# Flight_Controller.net
KiCad netlist of a schematic drawn in EAGLE
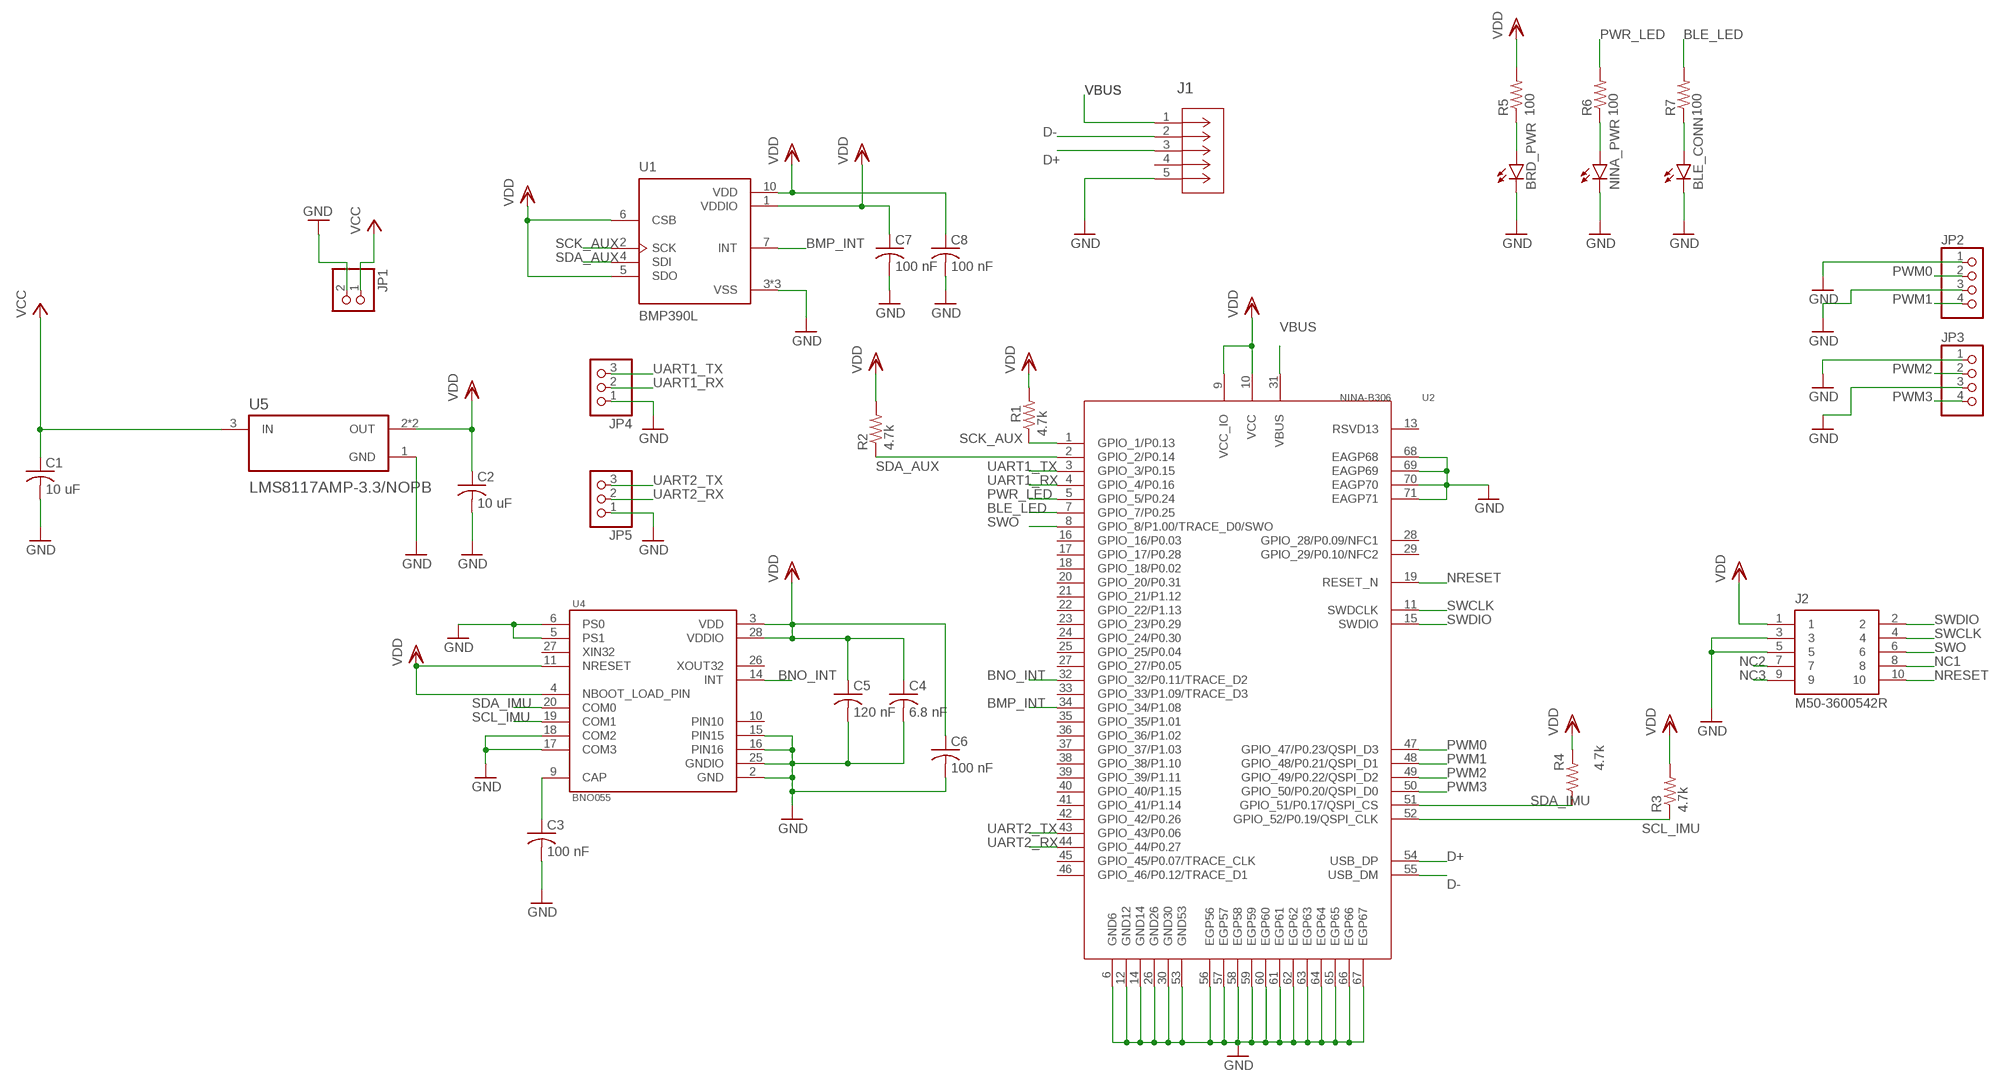
[diagram p0: schematic, sheet 1]

(export (version "E")
  (design (tool "Eeschema 10.0.6"))
  (components
    (comp (ref "BLE_CONN")
      (value "LEDCHIPLED_1206")
      (footprint "eagle-import:CHIPLED_1206")
      (libsource (lib "eagle-import") (part "LEDCHIPLED_1206"))
    )
    (comp (ref "BRD_PWR")
      (value "LEDCHIPLED_1206")
      (footprint "eagle-import:CHIPLED_1206")
      (libsource (lib "eagle-import") (part "LEDCHIPLED_1206"))
    )
    (comp (ref "C1")
      (value "10 uF")
      (footprint "eagle-import:C1206")
      (libsource (lib "eagle-import") (part "C-USC1206"))
    )
    (comp (ref "C2")
      (value "10 uF")
      (footprint "eagle-import:C1206")
      (libsource (lib "eagle-import") (part "C-USC1206"))
    )
    (comp (ref "C3")
      (value "100 nF")
      (footprint "eagle-import:C1206")
      (libsource (lib "eagle-import") (part "C-USC1206"))
    )
    (comp (ref "C4")
      (value "6.8 nF")
      (footprint "eagle-import:C1206")
      (libsource (lib "eagle-import") (part "C-USC1206"))
    )
    (comp (ref "C5")
      (value "120 nF")
      (footprint "eagle-import:C1206")
      (libsource (lib "eagle-import") (part "C-USC1206"))
    )
    (comp (ref "C6")
      (value "100 nF")
      (footprint "eagle-import:C1206")
      (libsource (lib "eagle-import") (part "C-USC1206"))
    )
    (comp (ref "C7")
      (value "100 nF")
      (footprint "eagle-import:C1206")
      (libsource (lib "eagle-import") (part "C-USC1206"))
    )
    (comp (ref "C8")
      (value "100 nF")
      (footprint "eagle-import:C1206")
      (libsource (lib "eagle-import") (part "C-USC1206"))
    )
    (comp (ref "J1")
      (value "ZX62-AB-5PA(31)")
      (footprint "eagle-import:CONN5_ZX62-AB-5PA_HIR")
      (fields (field (name "COPYRIGHT") "Copyright (C) 2022 Ultra Librarian. All rights reserved."))
      (libsource (lib "eagle-import") (part "ZX62-AB-5PA(31)"))
    )
    (comp (ref "J2")
      (value "M50-3600542R")
      (footprint "eagle-import:HARWIN_M50-3600542R")
      (fields (field (name "MF") "Harwin Inc."))
      (libsource (lib "eagle-import") (part "M50-3600542R"))
    )
    (comp (ref "JP1")
      (value "PINHD-1X2")
      (footprint "eagle-import:1X02")
      (libsource (lib "eagle-import") (part "PINHD-1X2"))
    )
    (comp (ref "JP2")
      (value "PINHD-1X4")
      (footprint "eagle-import:1X04")
      (libsource (lib "eagle-import") (part "PINHD-1X4"))
    )
    (comp (ref "JP3")
      (value "PINHD-1X4")
      (footprint "eagle-import:1X04")
      (libsource (lib "eagle-import") (part "PINHD-1X4"))
    )
    (comp (ref "JP4")
      (value "PINHD-1X3")
      (footprint "eagle-import:1X03")
      (libsource (lib "eagle-import") (part "PINHD-1X3"))
    )
    (comp (ref "JP5")
      (value "PINHD-1X3")
      (footprint "eagle-import:1X03")
      (libsource (lib "eagle-import") (part "PINHD-1X3"))
    )
    (comp (ref "NINA_PWR")
      (value "LEDCHIPLED_1206")
      (footprint "eagle-import:CHIPLED_1206")
      (libsource (lib "eagle-import") (part "LEDCHIPLED_1206"))
    )
    (comp (ref "R1")
      (value "4.7k")
      (footprint "eagle-import:R1206")
      (libsource (lib "eagle-import") (part "R-US_R1206"))
    )
    (comp (ref "R2")
      (value "4.7k")
      (footprint "eagle-import:R1206")
      (libsource (lib "eagle-import") (part "R-US_R1206"))
    )
    (comp (ref "R3")
      (value "4.7k")
      (footprint "eagle-import:R1206")
      (libsource (lib "eagle-import") (part "R-US_R1206"))
    )
    (comp (ref "R4")
      (value "4.7k")
      (footprint "eagle-import:R1206")
      (libsource (lib "eagle-import") (part "R-US_R1206"))
    )
    (comp (ref "R5")
      (value "100")
      (footprint "eagle-import:R1206")
      (libsource (lib "eagle-import") (part "R-US_R1206"))
    )
    (comp (ref "R6")
      (value "100")
      (footprint "eagle-import:R1206")
      (libsource (lib "eagle-import") (part "R-US_R1206"))
    )
    (comp (ref "R7")
      (value "100")
      (footprint "eagle-import:R1206")
      (libsource (lib "eagle-import") (part "R-US_R1206"))
    )
    (comp (ref "U1")
      (value "BMP390L")
      (footprint "eagle-import:XDCR_BMP390L")
      (fields (field (name "MF") "Bosch Sensortec"))
      (libsource (lib "eagle-import") (part "BMP390L"))
    )
    (comp (ref "U2")
      (value "NINA-B306")
      (footprint "eagle-import:NINA_LGA71R_1500X1000X223_PCB")
      (fields (field (name "MANUFACTURER") "u-blox"))
      (libsource (lib "eagle-import") (part "NINA-B306NINA-B306_NINA_LGA71R_1500X1000X223_PCB"))
    )
    (comp (ref "U4")
      (value "BNO055")
      (footprint "eagle-import:LGA28R50P4X10_380X520X100")
      (fields (field (name "MF") "Bosch"))
      (libsource (lib "eagle-import") (part "BNO055"))
    )
    (comp (ref "U5")
      (value "LMS8117AMP-3.3/NOPB")
      (footprint "eagle-import:SOT230P700X180-4N")
      (fields (field (name "MF") "Texas Instruments"))
      (libsource (lib "eagle-import") (part "LMS8117AMP-3.3/NOPB"))
    )
  )
  (nets
    (net (code "1") (name "/BLE_LED") (class "Default")
      (node (ref "R7") (pin "2") (pinfunction "2_2") (pintype "passive"))
      (node (ref "U2") (pin "7") (pinfunction "GPIO_7/P0.25_7") (pintype "bidirectional"))
    )
    (net (code "2") (name "/BMP_INT") (class "Default")
      (node (ref "U1") (pin "7") (pinfunction "INT_7") (pintype "output"))
      (node (ref "U2") (pin "34") (pinfunction "GPIO_34/P1.08_34") (pintype "bidirectional"))
    )
    (net (code "3") (name "/BNO_INT") (class "Default")
      (node (ref "U2") (pin "32") (pinfunction "GPIO_32/P0.11/TRACE_D2_32") (pintype "bidirectional"))
      (node (ref "U4") (pin "14") (pinfunction "INT_14") (pintype "output"))
    )
    (net (code "4") (name "/D+") (class "Default")
      (node (ref "J1") (pin "3") (pinfunction "D+_3") (pintype "passive"))
      (node (ref "U2") (pin "54") (pinfunction "USB_DP_54") (pintype "bidirectional"))
    )
    (net (code "5") (name "/D-") (class "Default")
      (node (ref "J1") (pin "2") (pinfunction "D-_2") (pintype "passive"))
      (node (ref "U2") (pin "55") (pinfunction "USB_DM_55") (pintype "bidirectional"))
    )
    (net (code "6") (name "/NC1") (class "Default")
      (node (ref "J2") (pin "8") (pinfunction "8_8") (pintype "passive"))
    )
    (net (code "7") (name "/NC2") (class "Default")
      (node (ref "J2") (pin "7") (pinfunction "7_7") (pintype "passive"))
    )
    (net (code "8") (name "/NC3") (class "Default")
      (node (ref "J2") (pin "9") (pinfunction "9_9") (pintype "passive"))
    )
    (net (code "9") (name "/NRESET") (class "Default")
      (node (ref "J2") (pin "10") (pinfunction "10_10") (pintype "passive"))
      (node (ref "U2") (pin "19") (pinfunction "RESET_N_19") (pintype "input"))
    )
    (net (code "10") (name "/PIN10") (class "Default")
      (node (ref "U4") (pin "10") (pinfunction "PIN10_10") (pintype "power_in"))
    )
    (net (code "11") (name "/PWM0") (class "Default")
      (node (ref "JP2") (pin "2") (pinfunction "2_2") (pintype "passive"))
      (node (ref "U2") (pin "47") (pinfunction "GPIO_47/P0.23/QSPI_D3_47") (pintype "bidirectional"))
    )
    (net (code "12") (name "/PWM1") (class "Default")
      (node (ref "JP2") (pin "4") (pinfunction "4_4") (pintype "passive"))
      (node (ref "U2") (pin "48") (pinfunction "GPIO_48/P0.21/QSPI_D1_48") (pintype "bidirectional"))
    )
    (net (code "13") (name "/PWM2") (class "Default")
      (node (ref "JP3") (pin "2") (pinfunction "2_2") (pintype "passive"))
      (node (ref "U2") (pin "49") (pinfunction "GPIO_49/P0.22/QSPI_D2_49") (pintype "bidirectional"))
    )
    (net (code "14") (name "/PWM3") (class "Default")
      (node (ref "JP3") (pin "4") (pinfunction "4_4") (pintype "passive"))
      (node (ref "U2") (pin "50") (pinfunction "GPIO_50/P0.20/QSPI_D0_50") (pintype "bidirectional"))
    )
    (net (code "15") (name "/PWR_LED") (class "Default")
      (node (ref "R6") (pin "2") (pinfunction "2_2") (pintype "passive"))
      (node (ref "U2") (pin "5") (pinfunction "GPIO_5/P0.24_5") (pintype "bidirectional"))
    )
    (net (code "16") (name "/SCK_AUX") (class "Default")
      (node (ref "R1") (pin "1") (pinfunction "1_1") (pintype "passive"))
      (node (ref "U1") (pin "2") (pinfunction "SCK_2") (pintype "input"))
      (node (ref "U2") (pin "1") (pinfunction "GPIO_1/P0.13_1") (pintype "bidirectional"))
    )
    (net (code "17") (name "/SCL_IMU") (class "Default")
      (node (ref "R3") (pin "1") (pinfunction "1_1") (pintype "passive"))
      (node (ref "U2") (pin "52") (pinfunction "GPIO_52/P0.19/QSPI_CLK_52") (pintype "bidirectional"))
      (node (ref "U4") (pin "19") (pinfunction "COM1_19") (pintype "bidirectional"))
    )
    (net (code "18") (name "/SDA_AUX") (class "Default")
      (node (ref "R2") (pin "1") (pinfunction "1_1") (pintype "passive"))
      (node (ref "U1") (pin "4") (pinfunction "SDI_4") (pintype "input"))
      (node (ref "U2") (pin "2") (pinfunction "GPIO_2/P0.14_2") (pintype "bidirectional"))
    )
    (net (code "19") (name "/SDA_IMU") (class "Default")
      (node (ref "R4") (pin "1") (pinfunction "1_1") (pintype "passive"))
      (node (ref "U2") (pin "51") (pinfunction "GPIO_51/P0.17/QSPI_CS_51") (pintype "bidirectional"))
      (node (ref "U4") (pin "20") (pinfunction "COM0_20") (pintype "bidirectional"))
    )
    (net (code "20") (name "/SWCLK") (class "Default")
      (node (ref "J2") (pin "4") (pinfunction "4_4") (pintype "passive"))
      (node (ref "U2") (pin "11") (pinfunction "SWDCLK_11") (pintype "input"))
    )
    (net (code "21") (name "/SWDIO") (class "Default")
      (node (ref "J2") (pin "2") (pinfunction "2_2") (pintype "passive"))
      (node (ref "U2") (pin "15") (pinfunction "SWDIO_15") (pintype "bidirectional"))
    )
    (net (code "22") (name "/SWO") (class "Default")
      (node (ref "J2") (pin "6") (pinfunction "6_6") (pintype "passive"))
      (node (ref "U2") (pin "8") (pinfunction "GPIO_8/P1.00/TRACE_D0/SWO_8") (pintype "bidirectional"))
    )
    (net (code "23") (name "/UART1_RX") (class "Default")
      (node (ref "JP4") (pin "2") (pinfunction "2_2") (pintype "passive"))
      (node (ref "U2") (pin "4") (pinfunction "GPIO_4/P0.16_4") (pintype "bidirectional"))
    )
    (net (code "24") (name "/UART1_TX") (class "Default")
      (node (ref "JP4") (pin "3") (pinfunction "3_3") (pintype "passive"))
      (node (ref "U2") (pin "3") (pinfunction "GPIO_3/P0.15_3") (pintype "bidirectional"))
    )
    (net (code "25") (name "/UART2_RX") (class "Default")
      (node (ref "JP5") (pin "2") (pinfunction "2_2") (pintype "passive"))
      (node (ref "U2") (pin "44") (pinfunction "GPIO_44/P0.27_44") (pintype "bidirectional"))
    )
    (net (code "26") (name "/UART2_TX") (class "Default")
      (node (ref "JP5") (pin "3") (pinfunction "3_3") (pintype "passive"))
      (node (ref "U2") (pin "43") (pinfunction "GPIO_43/P0.06_43") (pintype "bidirectional"))
    )
    (net (code "27") (name "/VBUS") (class "Default")
      (node (ref "J1") (pin "1") (pinfunction "VCC_1") (pintype "passive"))
      (node (ref "U2") (pin "31") (pinfunction "VBUS_31") (pintype "power_in"))
    )
    (net (code "28") (name "GND") (class "Default")
      (node (ref "BLE_CONN") (pin "C") (pinfunction "C_C") (pintype "passive"))
      (node (ref "BRD_PWR") (pin "C") (pinfunction "C_C") (pintype "passive"))
      (node (ref "C1") (pin "2") (pinfunction "2_2") (pintype "passive"))
      (node (ref "C2") (pin "2") (pinfunction "2_2") (pintype "passive"))
      (node (ref "C3") (pin "2") (pinfunction "2_2") (pintype "passive"))
      (node (ref "C4") (pin "2") (pinfunction "2_2") (pintype "passive"))
      (node (ref "C5") (pin "2") (pinfunction "2_2") (pintype "passive"))
      (node (ref "C6") (pin "2") (pinfunction "2_2") (pintype "passive"))
      (node (ref "C7") (pin "2") (pinfunction "2_2") (pintype "passive"))
      (node (ref "C8") (pin "2") (pinfunction "2_2") (pintype "passive"))
      (node (ref "J1") (pin "5") (pinfunction "GND_5") (pintype "passive"))
      (node (ref "J2") (pin "3") (pinfunction "3_3") (pintype "passive"))
      (node (ref "J2") (pin "5") (pinfunction "5_5") (pintype "passive"))
      (node (ref "JP1") (pin "2") (pinfunction "2_2") (pintype "passive"))
      (node (ref "JP2") (pin "1") (pinfunction "1_1") (pintype "passive"))
      (node (ref "JP2") (pin "3") (pinfunction "3_3") (pintype "passive"))
      (node (ref "JP3") (pin "1") (pinfunction "1_1") (pintype "passive"))
      (node (ref "JP3") (pin "3") (pinfunction "3_3") (pintype "passive"))
      (node (ref "JP4") (pin "1") (pinfunction "1_1") (pintype "passive"))
      (node (ref "JP5") (pin "1") (pinfunction "1_1") (pintype "passive"))
      (node (ref "NINA_PWR") (pin "C") (pinfunction "C_C") (pintype "passive"))
      (node (ref "U1") (pin "3") (pinfunction "VSS_3") (pintype "power_in"))
      (node (ref "U1") (pin "8") (pinfunction "VSS_8") (pintype "power_in"))
      (node (ref "U1") (pin "9") (pinfunction "VSS_9") (pintype "power_in"))
      (node (ref "U2") (pin "12") (pinfunction "GND12_12") (pintype "power_in"))
      (node (ref "U2") (pin "14") (pinfunction "GND14_14") (pintype "power_in"))
      (node (ref "U2") (pin "26") (pinfunction "GND26_26") (pintype "power_in"))
      (node (ref "U2") (pin "30") (pinfunction "GND30_30") (pintype "power_in"))
      (node (ref "U2") (pin "53") (pinfunction "GND53_53") (pintype "power_in"))
      (node (ref "U2") (pin "56") (pinfunction "EGP56_56") (pintype "power_in"))
      (node (ref "U2") (pin "57") (pinfunction "EGP57_57") (pintype "power_in"))
      (node (ref "U2") (pin "58") (pinfunction "EGP58_58") (pintype "power_in"))
      (node (ref "U2") (pin "59") (pinfunction "EGP59_59") (pintype "power_in"))
      (node (ref "U2") (pin "6") (pinfunction "GND6_6") (pintype "power_in"))
      (node (ref "U2") (pin "60") (pinfunction "EGP60_60") (pintype "power_in"))
      (node (ref "U2") (pin "61") (pinfunction "EGP61_61") (pintype "power_in"))
      (node (ref "U2") (pin "62") (pinfunction "EGP62_62") (pintype "power_in"))
      (node (ref "U2") (pin "63") (pinfunction "EGP63_63") (pintype "power_in"))
      (node (ref "U2") (pin "64") (pinfunction "EGP64_64") (pintype "power_in"))
      (node (ref "U2") (pin "65") (pinfunction "EGP65_65") (pintype "power_in"))
      (node (ref "U2") (pin "66") (pinfunction "EGP66_66") (pintype "power_in"))
      (node (ref "U2") (pin "67") (pinfunction "EGP67_67") (pintype "power_in"))
      (node (ref "U2") (pin "68") (pinfunction "EAGP68_68") (pintype "power_in"))
      (node (ref "U2") (pin "69") (pinfunction "EAGP69_69") (pintype "power_in"))
      (node (ref "U2") (pin "70") (pinfunction "EAGP70_70") (pintype "power_in"))
      (node (ref "U2") (pin "71") (pinfunction "EAGP71_71") (pintype "power_in"))
      (node (ref "U4") (pin "15") (pinfunction "PIN15_15") (pintype "power_in"))
      (node (ref "U4") (pin "16") (pinfunction "PIN16_16") (pintype "power_in"))
      (node (ref "U4") (pin "17") (pinfunction "COM3_17") (pintype "bidirectional"))
      (node (ref "U4") (pin "18") (pinfunction "COM2_18") (pintype "bidirectional"))
      (node (ref "U4") (pin "2") (pinfunction "GND_2") (pintype "power_in"))
      (node (ref "U4") (pin "25") (pinfunction "GNDIO_25") (pintype "power_in"))
      (node (ref "U4") (pin "5") (pinfunction "PS1_5") (pintype "input"))
      (node (ref "U4") (pin "6") (pinfunction "PS0_6") (pintype "input"))
      (node (ref "U5") (pin "1") (pinfunction "GND_1") (pintype "power_in"))
    )
    (net (code "29") (name "Net-(BLE_CONN-PadA)") (class "Default")
      (node (ref "BLE_CONN") (pin "A") (pinfunction "A_A") (pintype "passive"))
      (node (ref "R7") (pin "1") (pinfunction "1_1") (pintype "passive"))
    )
    (net (code "30") (name "Net-(BRD_PWR-PadA)") (class "Default")
      (node (ref "BRD_PWR") (pin "A") (pinfunction "A_A") (pintype "passive"))
      (node (ref "R5") (pin "1") (pinfunction "1_1") (pintype "passive"))
    )
    (net (code "31") (name "Net-(NINA_PWR-PadA)") (class "Default")
      (node (ref "NINA_PWR") (pin "A") (pinfunction "A_A") (pintype "passive"))
      (node (ref "R6") (pin "1") (pinfunction "1_1") (pintype "passive"))
    )
    (net (code "32") (name "Net-(U4-CAP)") (class "Default")
      (node (ref "C3") (pin "1") (pinfunction "1_1") (pintype "passive"))
      (node (ref "U4") (pin "9") (pinfunction "CAP_9") (pintype "passive"))
    )
    (net (code "33") (name "VCC") (class "Default")
      (node (ref "C1") (pin "1") (pinfunction "1_1") (pintype "passive"))
      (node (ref "JP1") (pin "1") (pinfunction "1_1") (pintype "passive"))
      (node (ref "U5") (pin "3") (pinfunction "IN_3") (pintype "input"))
    )
    (net (code "34") (name "VDD") (class "Default")
      (node (ref "C2") (pin "1") (pinfunction "1_1") (pintype "passive"))
      (node (ref "C4") (pin "1") (pinfunction "1_1") (pintype "passive"))
      (node (ref "C5") (pin "1") (pinfunction "1_1") (pintype "passive"))
      (node (ref "C6") (pin "1") (pinfunction "1_1") (pintype "passive"))
      (node (ref "C7") (pin "1") (pinfunction "1_1") (pintype "passive"))
      (node (ref "C8") (pin "1") (pinfunction "1_1") (pintype "passive"))
      (node (ref "J2") (pin "1") (pinfunction "1_1") (pintype "passive"))
      (node (ref "R1") (pin "2") (pinfunction "2_2") (pintype "passive"))
      (node (ref "R2") (pin "2") (pinfunction "2_2") (pintype "passive"))
      (node (ref "R3") (pin "2") (pinfunction "2_2") (pintype "passive"))
      (node (ref "R4") (pin "2") (pinfunction "2_2") (pintype "passive"))
      (node (ref "R5") (pin "2") (pinfunction "2_2") (pintype "passive"))
      (node (ref "U1") (pin "1") (pinfunction "VDDIO_1") (pintype "power_in"))
      (node (ref "U1") (pin "10") (pinfunction "VDD_10") (pintype "power_in"))
      (node (ref "U1") (pin "5") (pinfunction "SDO_5") (pintype "output"))
      (node (ref "U1") (pin "6") (pinfunction "CSB_6") (pintype "input"))
      (node (ref "U2") (pin "10") (pinfunction "VCC_10") (pintype "power_in"))
      (node (ref "U2") (pin "9") (pinfunction "VCC_IO_9") (pintype "power_in"))
      (node (ref "U4") (pin "11") (pinfunction "NRESET_11") (pintype "input"))
      (node (ref "U4") (pin "28") (pinfunction "VDDIO_28") (pintype "power_in"))
      (node (ref "U4") (pin "3") (pinfunction "VDD_3") (pintype "power_in"))
      (node (ref "U4") (pin "4") (pinfunction "NBOOT_LOAD_PIN_4") (pintype "bidirectional"))
      (node (ref "U5") (pin "2") (pinfunction "OUT_2") (pintype "output"))
      (node (ref "U5") (pin "4") (pinfunction "OUT_4") (pintype "output"))
    )
    (net (code "35") (name "unconnected-(J1-ID-Pad4)") (class "Default")
      (node (ref "J1") (pin "4") (pinfunction "ID_4") (pintype "passive"))
    )
    (net (code "36") (name "unconnected-(U2-GPIO_16{slash}P0.03-Pad16)") (class "Default")
      (node (ref "U2") (pin "16") (pinfunction "GPIO_16/P0.03_16") (pintype "bidirectional"))
    )
    (net (code "37") (name "unconnected-(U2-GPIO_17{slash}P0.28-Pad17)") (class "Default")
      (node (ref "U2") (pin "17") (pinfunction "GPIO_17/P0.28_17") (pintype "bidirectional"))
    )
    (net (code "38") (name "unconnected-(U2-GPIO_18{slash}P0.02-Pad18)") (class "Default")
      (node (ref "U2") (pin "18") (pinfunction "GPIO_18/P0.02_18") (pintype "bidirectional"))
    )
    (net (code "39") (name "unconnected-(U2-GPIO_20{slash}P0.31-Pad20)") (class "Default")
      (node (ref "U2") (pin "20") (pinfunction "GPIO_20/P0.31_20") (pintype "bidirectional"))
    )
    (net (code "40") (name "unconnected-(U2-GPIO_21{slash}P1.12-Pad21)") (class "Default")
      (node (ref "U2") (pin "21") (pinfunction "GPIO_21/P1.12_21") (pintype "bidirectional"))
    )
    (net (code "41") (name "unconnected-(U2-GPIO_22{slash}P1.13-Pad22)") (class "Default")
      (node (ref "U2") (pin "22") (pinfunction "GPIO_22/P1.13_22") (pintype "bidirectional"))
    )
    (net (code "42") (name "unconnected-(U2-GPIO_23{slash}P0.29-Pad23)") (class "Default")
      (node (ref "U2") (pin "23") (pinfunction "GPIO_23/P0.29_23") (pintype "bidirectional"))
    )
    (net (code "43") (name "unconnected-(U2-GPIO_24{slash}P0.30-Pad24)") (class "Default")
      (node (ref "U2") (pin "24") (pinfunction "GPIO_24/P0.30_24") (pintype "bidirectional"))
    )
    (net (code "44") (name "unconnected-(U2-GPIO_25{slash}P0.04-Pad25)") (class "Default")
      (node (ref "U2") (pin "25") (pinfunction "GPIO_25/P0.04_25") (pintype "bidirectional"))
    )
    (net (code "45") (name "unconnected-(U2-GPIO_27{slash}P0.05-Pad27)") (class "Default")
      (node (ref "U2") (pin "27") (pinfunction "GPIO_27/P0.05_27") (pintype "bidirectional"))
    )
    (net (code "46") (name "unconnected-(U2-GPIO_28{slash}P0.09{slash}NFC1-Pad28)") (class "Default")
      (node (ref "U2") (pin "28") (pinfunction "GPIO_28/P0.09/NFC1_28") (pintype "bidirectional"))
    )
    (net (code "47") (name "unconnected-(U2-GPIO_29{slash}P0.10{slash}NFC2-Pad29)") (class "Default")
      (node (ref "U2") (pin "29") (pinfunction "GPIO_29/P0.10/NFC2_29") (pintype "bidirectional"))
    )
    (net (code "48") (name "unconnected-(U2-GPIO_33{slash}P1.09{slash}TRACE_D3-Pad33)") (class "Default")
      (node (ref "U2") (pin "33") (pinfunction "GPIO_33/P1.09/TRACE_D3_33") (pintype "bidirectional"))
    )
    (net (code "49") (name "unconnected-(U2-GPIO_35{slash}P1.01-Pad35)") (class "Default")
      (node (ref "U2") (pin "35") (pinfunction "GPIO_35/P1.01_35") (pintype "bidirectional"))
    )
    (net (code "50") (name "unconnected-(U2-GPIO_36{slash}P1.02-Pad36)") (class "Default")
      (node (ref "U2") (pin "36") (pinfunction "GPIO_36/P1.02_36") (pintype "bidirectional"))
    )
    (net (code "51") (name "unconnected-(U2-GPIO_37{slash}P1.03-Pad37)") (class "Default")
      (node (ref "U2") (pin "37") (pinfunction "GPIO_37/P1.03_37") (pintype "bidirectional"))
    )
    (net (code "52") (name "unconnected-(U2-GPIO_38{slash}P1.10-Pad38)") (class "Default")
      (node (ref "U2") (pin "38") (pinfunction "GPIO_38/P1.10_38") (pintype "bidirectional"))
    )
    (net (code "53") (name "unconnected-(U2-GPIO_39{slash}P1.11-Pad39)") (class "Default")
      (node (ref "U2") (pin "39") (pinfunction "GPIO_39/P1.11_39") (pintype "bidirectional"))
    )
    (net (code "54") (name "unconnected-(U2-GPIO_40{slash}P1.15-Pad40)") (class "Default")
      (node (ref "U2") (pin "40") (pinfunction "GPIO_40/P1.15_40") (pintype "bidirectional"))
    )
    (net (code "55") (name "unconnected-(U2-GPIO_41{slash}P1.14-Pad41)") (class "Default")
      (node (ref "U2") (pin "41") (pinfunction "GPIO_41/P1.14_41") (pintype "bidirectional"))
    )
    (net (code "56") (name "unconnected-(U2-GPIO_42{slash}P0.26-Pad42)") (class "Default")
      (node (ref "U2") (pin "42") (pinfunction "GPIO_42/P0.26_42") (pintype "bidirectional"))
    )
    (net (code "57") (name "unconnected-(U2-GPIO_45{slash}P0.07{slash}TRACE_CLK-Pad45)") (class "Default")
      (node (ref "U2") (pin "45") (pinfunction "GPIO_45/P0.07/TRACE_CLK_45") (pintype "bidirectional"))
    )
    (net (code "58") (name "unconnected-(U2-GPIO_46{slash}P0.12{slash}TRACE_D1-Pad46)") (class "Default")
      (node (ref "U2") (pin "46") (pinfunction "GPIO_46/P0.12/TRACE_D1_46") (pintype "bidirectional"))
    )
    (net (code "59") (name "unconnected-(U2-RSVD13-Pad13)") (class "Default")
      (node (ref "U2") (pin "13") (pinfunction "RSVD13_13") (pintype "passive"))
    )
    (net (code "60") (name "unconnected-(U4-XIN32-Pad27)") (class "Default")
      (node (ref "U4") (pin "27") (pinfunction "XIN32_27") (pintype "input"))
    )
    (net (code "61") (name "unconnected-(U4-XOUT32-Pad26)") (class "Default")
      (node (ref "U4") (pin "26") (pinfunction "XOUT32_26") (pintype "output"))
    )
  )
)
